# fullflex-1.net
KiCad netlist of a schematic drawn in Altium Designer
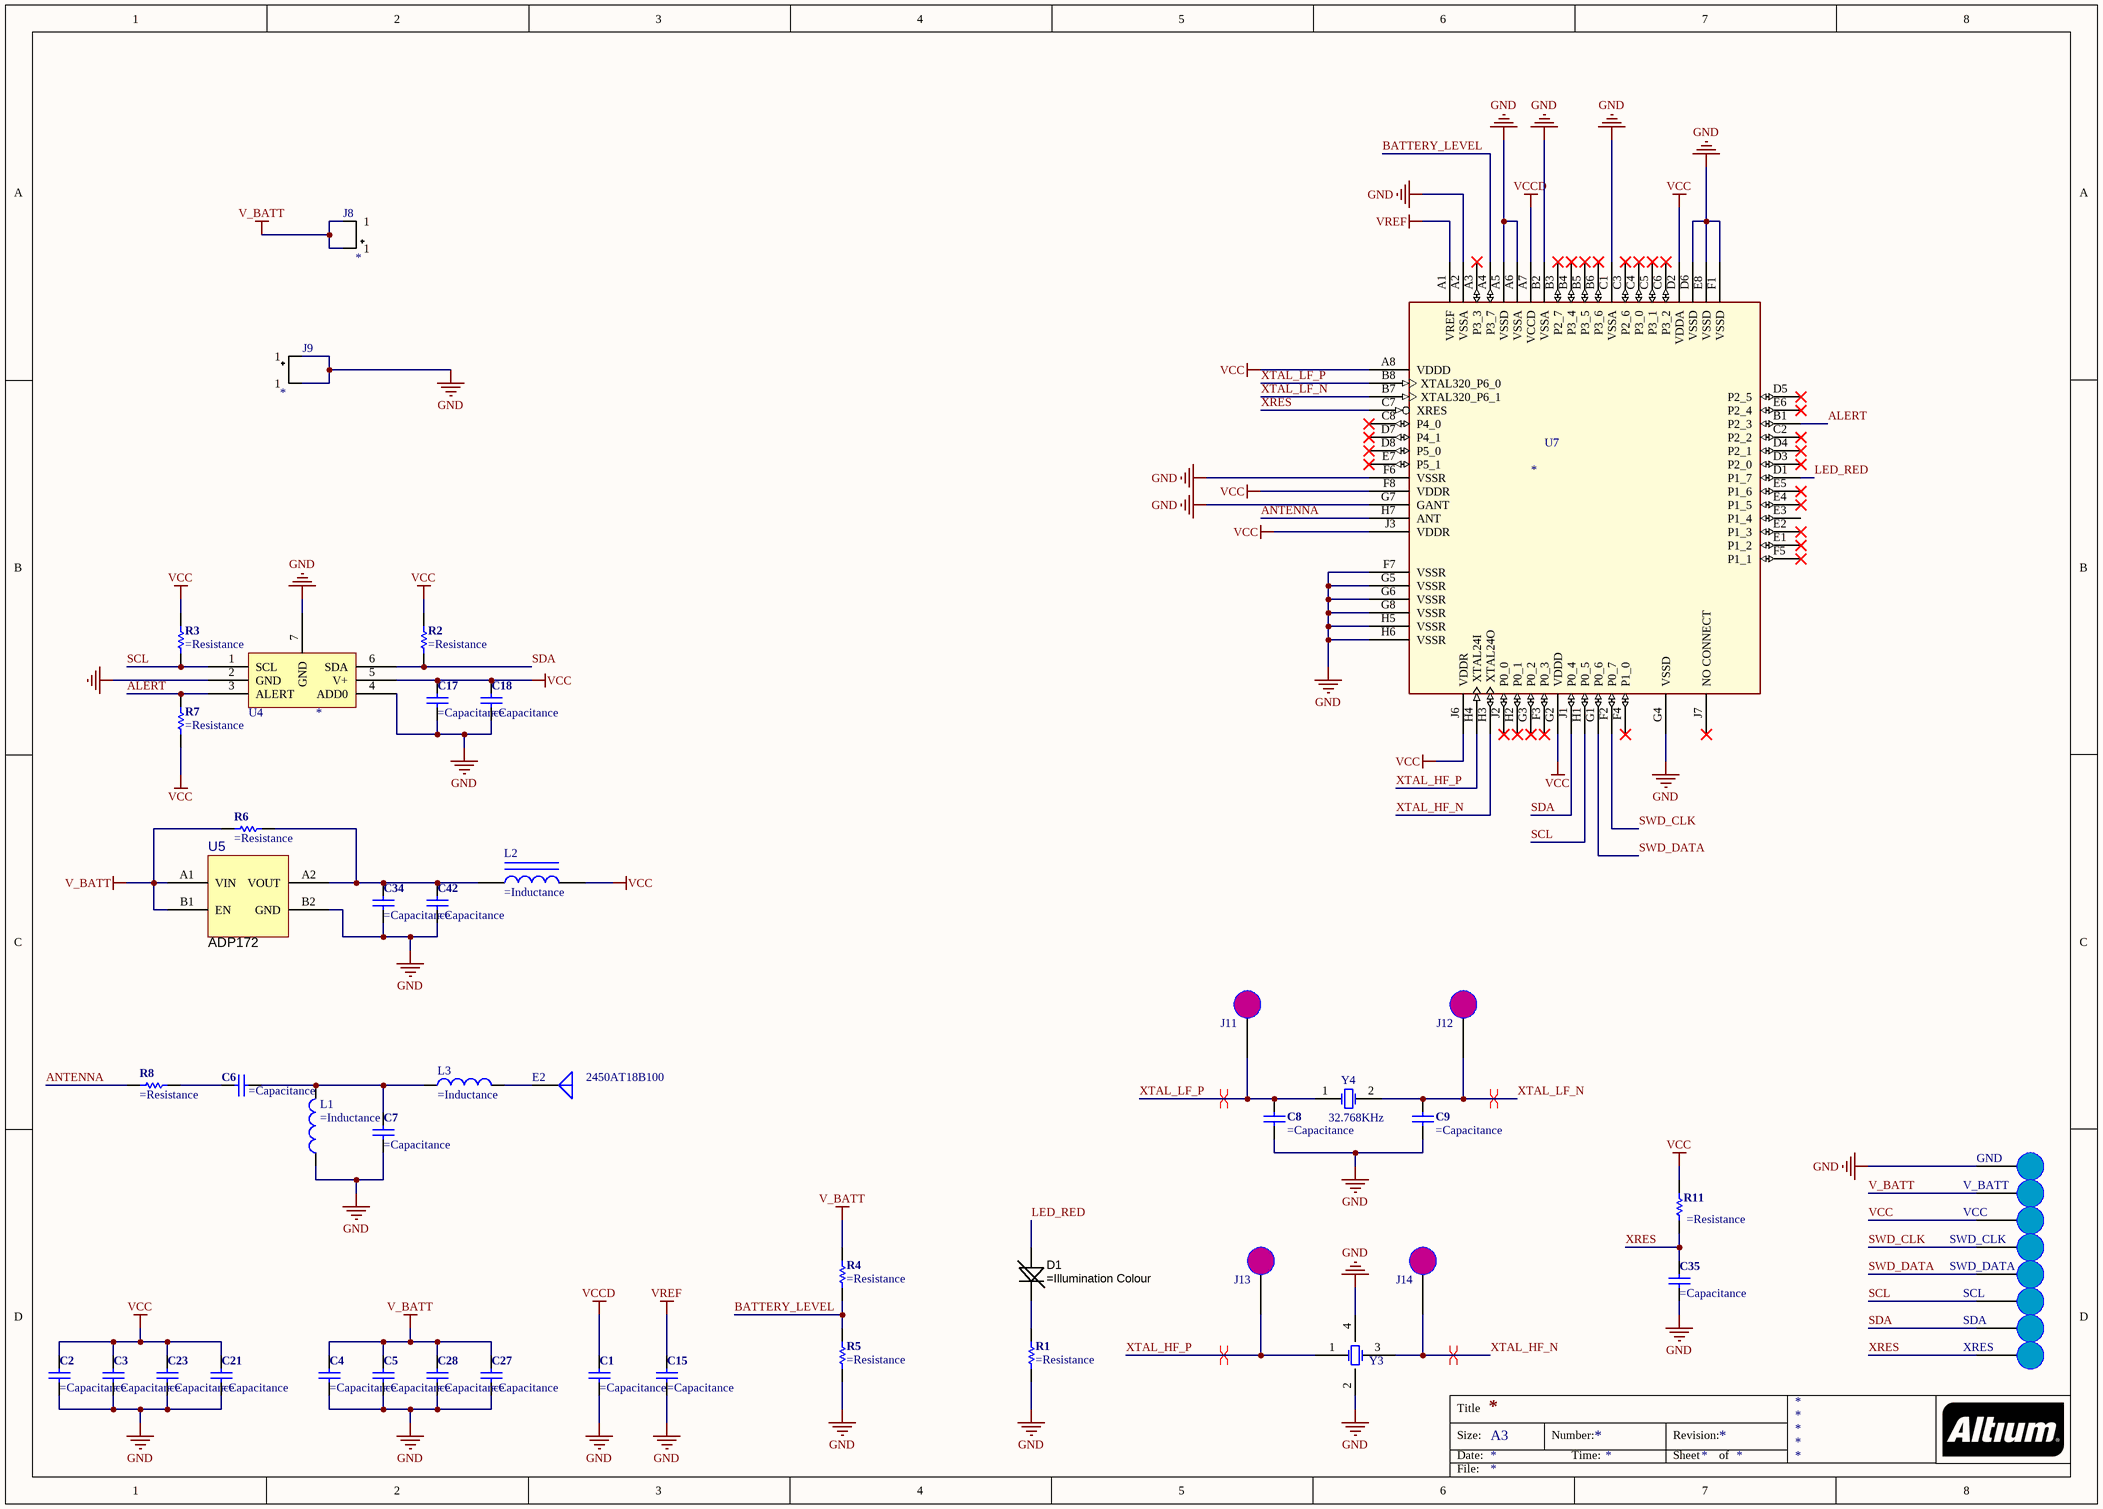
[diagram p0: fullflex-1.SchDoc]

(export (version "E")
  (design (tool "Eeschema 10.0.6"))
  (components
    (comp (ref "C1")
      (value "~")
      (footprint "CAP_0201(0603)_M")
      (description "___ OHM ___ mW 0201(0603) SMD")
      (libsource (lib "tempsensor") (part "C-0201(0603)"))
    )
    (comp (ref "C2")
      (value "~")
      (footprint "CAP_0402(1005)_M")
      (description "___ OHM ___ mW 0402(1005) SMD")
      (libsource (lib "tempsensor") (part "C-0402(1005)"))
    )
    (comp (ref "C3")
      (value "~")
      (footprint "CAP_0402(1005)_M")
      (description "___ OHM ___ mW 0402(1005) SMD")
      (libsource (lib "tempsensor") (part "C-0402(1005)"))
    )
    (comp (ref "C4")
      (value "~")
      (footprint "CAP_0402(1005)_M")
      (description "___ OHM ___ mW 0402(1005) SMD")
      (libsource (lib "tempsensor") (part "C-0402(1005)"))
    )
    (comp (ref "C5")
      (value "~")
      (footprint "CAP_0402(1005)_M")
      (description "___ OHM ___ mW 0402(1005) SMD")
      (libsource (lib "tempsensor") (part "C-0402(1005)"))
    )
    (comp (ref "C6")
      (value "~")
      (footprint "CAP_0402(1005)_M")
      (description "___ OHM ___ mW 0402(1005) SMD")
      (libsource (lib "tempsensor") (part "C-0402(1005)"))
    )
    (comp (ref "C7")
      (value "~")
      (footprint "CAP_0402(1005)_M")
      (description "___ OHM ___ mW 0402(1005) SMD")
      (libsource (lib "tempsensor") (part "C-0402(1005)"))
    )
    (comp (ref "C8")
      (value "~")
      (footprint "CAP_0402(1005)_M")
      (description "___ OHM ___ mW 0402(1005) SMD")
      (libsource (lib "tempsensor") (part "C-0402(1005)"))
    )
    (comp (ref "C9")
      (value "~")
      (footprint "CAP_0402(1005)_M")
      (description "___ OHM ___ mW 0402(1005) SMD")
      (libsource (lib "tempsensor") (part "C-0402(1005)"))
    )
    (comp (ref "C15")
      (value "~")
      (footprint "CAP_0201(0603)_M")
      (description "___ OHM ___ mW 0201(0603) SMD")
      (libsource (lib "tempsensor") (part "C-0201(0603)"))
    )
    (comp (ref "C17")
      (value "~")
      (footprint "CAP_0201(0603)_M")
      (description "___ OHM ___ mW 0201(0603) SMD")
      (libsource (lib "tempsensor") (part "C-0201(0603)"))
    )
    (comp (ref "C18")
      (value "~")
      (footprint "CAP_0201(0603)_M")
      (description "___ OHM ___ mW 0201(0603) SMD")
      (libsource (lib "tempsensor") (part "C-0201(0603)"))
    )
    (comp (ref "C21")
      (value "~")
      (footprint "CAP_0201(0603)_M")
      (description "___ OHM ___ mW 0201(0603) SMD")
      (libsource (lib "tempsensor") (part "C-0201(0603)"))
    )
    (comp (ref "C23")
      (value "~")
      (footprint "CAP_0201(0603)_M")
      (description "___ OHM ___ mW 0201(0603) SMD")
      (libsource (lib "tempsensor") (part "C-0201(0603)"))
    )
    (comp (ref "C27")
      (value "~")
      (footprint "CAP_0201(0603)_M")
      (description "___ OHM ___ mW 0201(0603) SMD")
      (libsource (lib "tempsensor") (part "C-0201(0603)"))
    )
    (comp (ref "C28")
      (value "~")
      (footprint "CAP_0201(0603)_M")
      (description "___ OHM ___ mW 0201(0603) SMD")
      (libsource (lib "tempsensor") (part "C-0201(0603)"))
    )
    (comp (ref "C34")
      (value "~")
      (footprint "CAP_0201(0603)_M")
      (description "___ OHM ___ mW 0201(0603) SMD")
      (libsource (lib "tempsensor") (part "C-0201(0603)"))
    )
    (comp (ref "C35")
      (value "~")
      (footprint "CAP_0201(0603)_M")
      (description "___ OHM ___ mW 0201(0603) SMD")
      (libsource (lib "tempsensor") (part "C-0201(0603)"))
    )
    (comp (ref "C42")
      (value "~")
      (footprint "CAP_0201(0603)_M")
      (description "___ OHM ___ mW 0201(0603) SMD")
      (libsource (lib "tempsensor") (part "C-0201(0603)"))
    )
    (comp (ref "D1")
      (value "~")
      (footprint "LED_0402(1005)")
      (description "LED, 0402(1005) SMD")
      (libsource (lib "tempsensor") (part "LED_0402(1005)"))
    )
    (comp (ref "E2")
      (value "2450AT18B100")
      (footprint "2450AT18B100")
      (description "2.4 GHz BLE Antenna")
      (fields
        (field (name "MANUFACTURER") "Johanson")
        (field (name "MANUFACTURER PART NUMBER") "2450AT18B100E")
      )
      (libsource (lib "tempsensor") (part "2450AT18B100"))
    )
    (comp (ref "GND")
      (value "*")
      (footprint "Pogo-Pin-Pad")
      (libsource (lib "tempsensor") (part "Probe-Pin Pad"))
    )
    (comp (ref "J8")
      (value "*")
      (footprint "Battery_PAD")
      (libsource (lib "tempsensor") (part "Battery_Connector"))
    )
    (comp (ref "J9")
      (value "*")
      (footprint "Battery_PAD")
      (libsource (lib "tempsensor") (part "Battery_Connector"))
    )
    (comp (ref "J11")
      (value "*")
      (footprint "Pogo-CLOCK-PAD")
      (libsource (lib "tempsensor") (part "Probe-CLOCK"))
    )
    (comp (ref "J12")
      (value "*")
      (footprint "Pogo-CLOCK-PAD")
      (libsource (lib "tempsensor") (part "Probe-CLOCK"))
    )
    (comp (ref "J13")
      (value "*")
      (footprint "Pogo-CLOCK-PAD")
      (libsource (lib "tempsensor") (part "Probe-CLOCK"))
    )
    (comp (ref "J14")
      (value "*")
      (footprint "Pogo-CLOCK-PAD")
      (libsource (lib "tempsensor") (part "Probe-CLOCK"))
    )
    (comp (ref "L1")
      (value "~")
      (footprint "IND_0402(1005)_M")
      (libsource (lib "tempsensor") (part "I-0402(1005)"))
    )
    (comp (ref "L2")
      (value "~")
      (footprint "IND_0402(1005)_M")
      (description "Magnetic-Core Inductor")
      (libsource (lib "tempsensor") (part "Inductor Iron"))
    )
    (comp (ref "L3")
      (value "~")
      (footprint "IND_0402(1005)_M")
      (libsource (lib "tempsensor") (part "I-0402(1005)"))
    )
    (comp (ref "R1")
      (value "~")
      (footprint "RES_0201(0603)_M")
      (description "___ OHM ___ mW 0201(0603) SMD")
      (libsource (lib "tempsensor") (part "R-0201(0603)"))
    )
    (comp (ref "R2")
      (value "~")
      (footprint "RES_0201(0603)_M")
      (description "___ OHM ___ mW 0201(0603) SMD")
      (libsource (lib "tempsensor") (part "R-0201(0603)"))
    )
    (comp (ref "R3")
      (value "~")
      (footprint "RES_0201(0603)_M")
      (description "___ OHM ___ mW 0201(0603) SMD")
      (libsource (lib "tempsensor") (part "R-0201(0603)"))
    )
    (comp (ref "R4")
      (value "~")
      (footprint "RES_0201(0603)_M")
      (description "___ OHM ___ mW 0201(0603) SMD")
      (libsource (lib "tempsensor") (part "R-0201(0603)"))
    )
    (comp (ref "R5")
      (value "~")
      (footprint "RES_0201(0603)_M")
      (description "___ OHM ___ mW 0201(0603) SMD")
      (libsource (lib "tempsensor") (part "R-0201(0603)"))
    )
    (comp (ref "R6")
      (value "~")
      (footprint "RES_0402(1005)_M")
      (description "___ OHM ___ mW 0402(1005) SMD")
      (libsource (lib "tempsensor") (part "R-0402(1005)"))
    )
    (comp (ref "R7")
      (value "~")
      (footprint "RES_0201(0603)_M")
      (description "___ OHM ___ mW 0201(0603) SMD")
      (libsource (lib "tempsensor") (part "R-0201(0603)"))
    )
    (comp (ref "R8")
      (value "~")
      (footprint "RES_0402(1005)_M")
      (description "___ OHM ___ mW 0402(1005) SMD")
      (libsource (lib "tempsensor") (part "R-0402(1005)"))
    )
    (comp (ref "R11")
      (value "~")
      (footprint "RES_0201(0603)_M")
      (description "___ OHM ___ mW 0201(0603) SMD")
      (libsource (lib "tempsensor") (part "R-0201(0603)"))
    )
    (comp (ref "SCL")
      (value "*")
      (footprint "Pogo-Pin-Pad")
      (libsource (lib "tempsensor") (part "Probe-Pin Pad"))
    )
    (comp (ref "SDA")
      (value "*")
      (footprint "Pogo-Pin-Pad")
      (libsource (lib "tempsensor") (part "Probe-Pin Pad"))
    )
    (comp (ref "SWD_CLK")
      (value "*")
      (footprint "Pogo-Pin-Pad")
      (libsource (lib "tempsensor") (part "Probe-Pin Pad"))
    )
    (comp (ref "SWD_DATA")
      (value "*")
      (footprint "Pogo-Pin-Pad")
      (libsource (lib "tempsensor") (part "Probe-Pin Pad"))
    )
    (comp (ref "U4")
      (value "*")
      (footprint "WSON-6")
      (description "TI Digital I2C Temperature Sensor")
      (fields
        (field (name "MANUFACTURER") "Texas Instruments")
        (field (name "MANUFACTURER PART NUMBER") "TMP116AIDRVT")
      )
      (libsource (lib "tempsensor") (part "TMP116"))
    )
    (comp (ref "U5")
      (value "ADP172")
      (footprint "ADP172")
      (description "3V LDO")
      (fields
        (field (name "MANUFACTURER") "Analog Devices")
        (field (name "MANUFACTURER PART NUMBER") "ADP172ACBZ-3.0-R7")
      )
      (libsource (lib "tempsensor") (part "ADP172"))
    )
    (comp (ref "U7")
      (value "*")
      (footprint "WLCSP-68")
      (description "PSOC 4 CYBLE")
      (fields
        (field (name "MANUFACTURER") "Cypress")
        (field (name "MANUFACTURER PART NUMBER") "CY8C4247FNI-BL483T")
      )
      (libsource (lib "tempsensor") (part "CY8C4127FNI-BL483"))
    )
    (comp (ref "VCC")
      (value "*")
      (footprint "Pogo-Pin-Pad")
      (libsource (lib "tempsensor") (part "Probe-Pin Pad"))
    )
    (comp (ref "V_BATT")
      (value "*")
      (footprint "Pogo-Pin-Pad")
      (libsource (lib "tempsensor") (part "Probe-Pin Pad"))
    )
    (comp (ref "XRES")
      (value "*")
      (footprint "Pogo-Pin-Pad")
      (libsource (lib "tempsensor") (part "Probe-Pin Pad"))
    )
    (comp (ref "Y3")
      (value "ECX-2236")
      (footprint "ECX-2236")
      (description "24 MHz Crystal")
      (fields
        (field (name "MANUFACTURER") "ECS International")
        (field (name "MANUFACTURER PART NUMBER") "ECS-240-8-36CKM-TR")
      )
      (libsource (lib "tempsensor") (part "ECX-2236"))
    )
    (comp (ref "Y4")
      (value "32.768KHz")
      (footprint "ABS05")
      (description "Crystal Oscillator")
      (fields
        (field (name "MANUFACTURER") "Abracon")
        (field (name "MANUFACTURER PART NUMBER") "ABS05-32.768KHZ-T")
      )
      (libsource (lib "tempsensor") (part "ABS05"))
    )
  )
  (nets
    (net (code "1") (name "/ALERT") (class "Default")
      (node (ref "R7") (pin "1") (pinfunction "1_1") (pintype "passive"))
      (node (ref "U4") (pin "3") (pinfunction "ALERT_3") (pintype "passive"))
      (node (ref "U7") (pin "B1") (pinfunction "P2_3_B1") (pintype "bidirectional"))
    )
    (net (code "2") (name "/ANTENNA") (class "Default")
      (node (ref "R8") (pin "1") (pinfunction "1_1") (pintype "passive"))
      (node (ref "U7") (pin "H7") (pinfunction "ANT_H7") (pintype "passive"))
    )
    (net (code "3") (name "/BATTERY_LEVEL") (class "Default")
      (node (ref "R4") (pin "2") (pinfunction "2_2") (pintype "passive"))
      (node (ref "R5") (pin "1") (pinfunction "1_1") (pintype "passive"))
      (node (ref "U7") (pin "A4") (pinfunction "P3_7_A4") (pintype "bidirectional"))
    )
    (net (code "4") (name "/LED_RED") (class "Default")
      (node (ref "D1") (pin "A") (pinfunction "A_A") (pintype "passive"))
      (node (ref "U7") (pin "D1") (pinfunction "P1_7_D1") (pintype "bidirectional"))
    )
    (net (code "5") (name "/SCL") (class "Default")
      (node (ref "R3") (pin "2") (pinfunction "2_2") (pintype "passive"))
      (node (ref "SCL") (pin "1") (pinfunction "1_1") (pintype "passive"))
      (node (ref "U4") (pin "1") (pinfunction "SCL_1") (pintype "passive"))
      (node (ref "U7") (pin "H1") (pinfunction "P0_5_H1") (pintype "bidirectional"))
    )
    (net (code "6") (name "/SDA") (class "Default")
      (node (ref "R2") (pin "2") (pinfunction "2_2") (pintype "passive"))
      (node (ref "SDA") (pin "1") (pinfunction "1_1") (pintype "passive"))
      (node (ref "U4") (pin "6") (pinfunction "SDA_6") (pintype "passive"))
      (node (ref "U7") (pin "J1") (pinfunction "P0_4_J1") (pintype "bidirectional"))
    )
    (net (code "7") (name "/SWD_CLK") (class "Default")
      (node (ref "SWD_CLK") (pin "1") (pinfunction "1_1") (pintype "passive"))
      (node (ref "U7") (pin "F2") (pinfunction "P0_7_F2") (pintype "bidirectional"))
    )
    (net (code "8") (name "/SWD_DATA") (class "Default")
      (node (ref "SWD_DATA") (pin "1") (pinfunction "1_1") (pintype "passive"))
      (node (ref "U7") (pin "G1") (pinfunction "P0_6_G1") (pintype "bidirectional"))
    )
    (net (code "9") (name "/XRES") (class "Default")
      (node (ref "C35") (pin "1") (pinfunction "1_1") (pintype "passive"))
      (node (ref "R11") (pin "2") (pinfunction "2_2") (pintype "passive"))
      (node (ref "U7") (pin "C7") (pinfunction "XRES_C7") (pintype "input"))
      (node (ref "XRES") (pin "1") (pinfunction "1_1") (pintype "passive"))
    )
    (net (code "10") (name "/XTAL_HF_N") (class "Default")
      (node (ref "J14") (pin "1") (pinfunction "1_1") (pintype "passive"))
      (node (ref "U7") (pin "H3") (pinfunction "XTAL24O_H3") (pintype "bidirectional"))
      (node (ref "Y3") (pin "3") (pinfunction "OSC2_3") (pintype "passive"))
    )
    (net (code "11") (name "/XTAL_HF_P") (class "Default")
      (node (ref "J13") (pin "1") (pinfunction "1_1") (pintype "passive"))
      (node (ref "U7") (pin "H4") (pinfunction "XTAL24I_H4") (pintype "input"))
      (node (ref "Y3") (pin "1") (pinfunction "OSC1_1") (pintype "passive"))
    )
    (net (code "12") (name "/XTAL_LF_N") (class "Default")
      (node (ref "C9") (pin "1") (pinfunction "1_1") (pintype "passive"))
      (node (ref "J12") (pin "1") (pinfunction "1_1") (pintype "passive"))
      (node (ref "U7") (pin "B7") (pinfunction "XTAL320_P6_1_B7") (pintype "input"))
      (node (ref "Y4") (pin "2") (pinfunction "OSC2_2") (pintype "passive"))
    )
    (net (code "13") (name "/XTAL_LF_P") (class "Default")
      (node (ref "C8") (pin "1") (pinfunction "1_1") (pintype "passive"))
      (node (ref "J11") (pin "1") (pinfunction "1_1") (pintype "passive"))
      (node (ref "U7") (pin "B8") (pinfunction "XTAL320_P6_0_B8") (pintype "input"))
      (node (ref "Y4") (pin "1") (pinfunction "OSC1_1") (pintype "passive"))
    )
    (net (code "14") (name "GND") (class "Default")
      (node (ref "C1") (pin "2") (pinfunction "2_2") (pintype "passive"))
      (node (ref "C15") (pin "2") (pinfunction "2_2") (pintype "passive"))
      (node (ref "C17") (pin "2") (pinfunction "2_2") (pintype "passive"))
      (node (ref "C18") (pin "2") (pinfunction "2_2") (pintype "passive"))
      (node (ref "C2") (pin "2") (pinfunction "2_2") (pintype "passive"))
      (node (ref "C21") (pin "2") (pinfunction "2_2") (pintype "passive"))
      (node (ref "C23") (pin "2") (pinfunction "2_2") (pintype "passive"))
      (node (ref "C27") (pin "2") (pinfunction "2_2") (pintype "passive"))
      (node (ref "C28") (pin "2") (pinfunction "2_2") (pintype "passive"))
      (node (ref "C3") (pin "2") (pinfunction "2_2") (pintype "passive"))
      (node (ref "C34") (pin "2") (pinfunction "2_2") (pintype "passive"))
      (node (ref "C35") (pin "2") (pinfunction "2_2") (pintype "passive"))
      (node (ref "C4") (pin "2") (pinfunction "2_2") (pintype "passive"))
      (node (ref "C42") (pin "2") (pinfunction "2_2") (pintype "passive"))
      (node (ref "C5") (pin "2") (pinfunction "2_2") (pintype "passive"))
      (node (ref "C7") (pin "2") (pinfunction "2_2") (pintype "passive"))
      (node (ref "C8") (pin "2") (pinfunction "2_2") (pintype "passive"))
      (node (ref "C9") (pin "2") (pinfunction "2_2") (pintype "passive"))
      (node (ref "GND") (pin "1") (pinfunction "1_1") (pintype "passive"))
      (node (ref "J9") (pin "1") (pinfunction "1_1") (pintype "passive"))
      (node (ref "L1") (pin "1") (pinfunction "1_1") (pintype "passive"))
      (node (ref "R1") (pin "2") (pinfunction "2_2") (pintype "passive"))
      (node (ref "R5") (pin "2") (pinfunction "2_2") (pintype "passive"))
      (node (ref "U4") (pin "2") (pinfunction "GND_2") (pintype "passive"))
      (node (ref "U4") (pin "4") (pinfunction "ADD0_4") (pintype "passive"))
      (node (ref "U4") (pin "7") (pinfunction "GND_7") (pintype "passive"))
      (node (ref "U5") (pin "B2") (pinfunction "GND_B2") (pintype "passive"))
      (node (ref "U7") (pin "A2") (pinfunction "VSSA_A2") (pintype "power_in"))
      (node (ref "U7") (pin "A5") (pinfunction "VSSD_A5") (pintype "power_in"))
      (node (ref "U7") (pin "A6") (pinfunction "VSSA_A6") (pintype "power_in"))
      (node (ref "U7") (pin "B2") (pinfunction "VSSA_B2") (pintype "power_in"))
      (node (ref "U7") (pin "C1") (pinfunction "VSSA_C1") (pintype "power_in"))
      (node (ref "U7") (pin "D6") (pinfunction "VSSD_D6") (pintype "power_in"))
      (node (ref "U7") (pin "E8") (pinfunction "VSSD_E8") (pintype "power_in"))
      (node (ref "U7") (pin "F1") (pinfunction "VSSD_F1") (pintype "power_in"))
      (node (ref "U7") (pin "F6") (pinfunction "VSSR_F6") (pintype "power_in"))
      (node (ref "U7") (pin "F7") (pinfunction "VSSR_F7") (pintype "power_in"))
      (node (ref "U7") (pin "G4") (pinfunction "VSSD_G4") (pintype "power_in"))
      (node (ref "U7") (pin "G5") (pinfunction "VSSR_G5") (pintype "power_in"))
      (node (ref "U7") (pin "G6") (pinfunction "VSSR_G6") (pintype "power_in"))
      (node (ref "U7") (pin "G7") (pinfunction "GANT_G7") (pintype "power_in"))
      (node (ref "U7") (pin "G8") (pinfunction "VSSR_G8") (pintype "power_in"))
      (node (ref "U7") (pin "H5") (pinfunction "VSSR_H5") (pintype "power_in"))
      (node (ref "U7") (pin "H6") (pinfunction "VSSR_H6") (pintype "power_in"))
      (node (ref "Y3") (pin "2") (pinfunction "GND_2") (pintype "passive"))
      (node (ref "Y3") (pin "4") (pinfunction "GND_4") (pintype "passive"))
    )
    (net (code "15") (name "Net-(C6-Pad1)") (class "Default")
      (node (ref "C6") (pin "1") (pinfunction "1_1") (pintype "passive"))
      (node (ref "R8") (pin "2") (pinfunction "2_2") (pintype "passive"))
    )
    (net (code "16") (name "Net-(C6-Pad2)") (class "Default")
      (node (ref "C6") (pin "2") (pinfunction "2_2") (pintype "passive"))
      (node (ref "C7") (pin "1") (pinfunction "1_1") (pintype "passive"))
      (node (ref "L1") (pin "2") (pinfunction "2_2") (pintype "passive"))
      (node (ref "L3") (pin "1") (pinfunction "1_1") (pintype "passive"))
    )
    (net (code "17") (name "Net-(D1-PadK)") (class "Default")
      (node (ref "D1") (pin "K") (pinfunction "K_K") (pintype "passive"))
      (node (ref "R1") (pin "1") (pinfunction "1_1") (pintype "passive"))
    )
    (net (code "18") (name "Net-(E2-A)") (class "Default")
      (node (ref "E2") (pin "1") (pinfunction "A_1") (pintype "passive"))
      (node (ref "L3") (pin "2") (pinfunction "2_2") (pintype "passive"))
    )
    (net (code "19") (name "Net-(U5-VOUT)") (class "Default")
      (node (ref "C34") (pin "1") (pinfunction "1_1") (pintype "passive"))
      (node (ref "C42") (pin "1") (pinfunction "1_1") (pintype "passive"))
      (node (ref "L2") (pin "1") (pinfunction "1_1") (pintype "passive"))
      (node (ref "R6") (pin "2") (pinfunction "2_2") (pintype "passive"))
      (node (ref "U5") (pin "A2") (pinfunction "VOUT_A2") (pintype "passive"))
    )
    (net (code "20") (name "VCC") (class "Default")
      (node (ref "C17") (pin "1") (pinfunction "1_1") (pintype "passive"))
      (node (ref "C18") (pin "1") (pinfunction "1_1") (pintype "passive"))
      (node (ref "C2") (pin "1") (pinfunction "1_1") (pintype "passive"))
      (node (ref "C21") (pin "1") (pinfunction "1_1") (pintype "passive"))
      (node (ref "C23") (pin "1") (pinfunction "1_1") (pintype "passive"))
      (node (ref "C3") (pin "1") (pinfunction "1_1") (pintype "passive"))
      (node (ref "L2") (pin "2") (pinfunction "2_2") (pintype "passive"))
      (node (ref "R11") (pin "1") (pinfunction "1_1") (pintype "passive"))
      (node (ref "R2") (pin "1") (pinfunction "1_1") (pintype "passive"))
      (node (ref "R3") (pin "1") (pinfunction "1_1") (pintype "passive"))
      (node (ref "R7") (pin "2") (pinfunction "2_2") (pintype "passive"))
      (node (ref "U4") (pin "5") (pinfunction "V+_5") (pintype "passive"))
      (node (ref "U7") (pin "A8") (pinfunction "VDDD_A8") (pintype "power_in"))
      (node (ref "U7") (pin "D2") (pinfunction "VDDA_D2") (pintype "power_in"))
      (node (ref "U7") (pin "F8") (pinfunction "VDDR_F8") (pintype "power_in"))
      (node (ref "U7") (pin "G2") (pinfunction "VDDD_G2") (pintype "power_in"))
      (node (ref "U7") (pin "J3") (pinfunction "VDDR_J3") (pintype "power_in"))
      (node (ref "U7") (pin "J6") (pinfunction "VDDR_J6") (pintype "power_in"))
      (node (ref "VCC") (pin "1") (pinfunction "1_1") (pintype "passive"))
    )
    (net (code "21") (name "VCCD") (class "Default")
      (node (ref "C1") (pin "1") (pinfunction "1_1") (pintype "passive"))
      (node (ref "U7") (pin "A7") (pinfunction "VCCD_A7") (pintype "power_in"))
    )
    (net (code "22") (name "VREF") (class "Default")
      (node (ref "C15") (pin "1") (pinfunction "1_1") (pintype "passive"))
      (node (ref "U7") (pin "A1") (pinfunction "VREF_A1") (pintype "power_in"))
    )
    (net (code "23") (name "V_BATT") (class "Default")
      (node (ref "C27") (pin "1") (pinfunction "1_1") (pintype "passive"))
      (node (ref "C28") (pin "1") (pinfunction "1_1") (pintype "passive"))
      (node (ref "C4") (pin "1") (pinfunction "1_1") (pintype "passive"))
      (node (ref "C5") (pin "1") (pinfunction "1_1") (pintype "passive"))
      (node (ref "J8") (pin "1") (pinfunction "1_1") (pintype "passive"))
      (node (ref "R4") (pin "1") (pinfunction "1_1") (pintype "passive"))
      (node (ref "R6") (pin "1") (pinfunction "1_1") (pintype "passive"))
      (node (ref "U5") (pin "A1") (pinfunction "VIN_A1") (pintype "passive"))
      (node (ref "U5") (pin "B1") (pinfunction "EN_B1") (pintype "passive"))
      (node (ref "V_BATT") (pin "1") (pinfunction "1_1") (pintype "passive"))
    )
    (net (code "24") (name "unconnected-(U7-NO_CONNECT-PadJ7)") (class "Default")
      (node (ref "U7") (pin "J7") (pinfunction "NO_CONNECT_J7") (pintype "passive+no_connect"))
    )
    (net (code "25") (name "unconnected-(U7-P0_0-PadJ2)") (class "Default")
      (node (ref "U7") (pin "J2") (pinfunction "P0_0_J2") (pintype "bidirectional+no_connect"))
    )
    (net (code "26") (name "unconnected-(U7-P0_1-PadH2)") (class "Default")
      (node (ref "U7") (pin "H2") (pinfunction "P0_1_H2") (pintype "bidirectional+no_connect"))
    )
    (net (code "27") (name "unconnected-(U7-P0_2-PadG3)") (class "Default")
      (node (ref "U7") (pin "G3") (pinfunction "P0_2_G3") (pintype "bidirectional+no_connect"))
    )
    (net (code "28") (name "unconnected-(U7-P0_3-PadF3)") (class "Default")
      (node (ref "U7") (pin "F3") (pinfunction "P0_3_F3") (pintype "bidirectional+no_connect"))
    )
    (net (code "29") (name "unconnected-(U7-P1_0-PadF4)") (class "Default")
      (node (ref "U7") (pin "F4") (pinfunction "P1_0_F4") (pintype "bidirectional+no_connect"))
    )
    (net (code "30") (name "unconnected-(U7-P1_1-PadF5)") (class "Default")
      (node (ref "U7") (pin "F5") (pinfunction "P1_1_F5") (pintype "bidirectional+no_connect"))
    )
    (net (code "31") (name "unconnected-(U7-P1_2-PadE1)") (class "Default")
      (node (ref "U7") (pin "E1") (pinfunction "P1_2_E1") (pintype "bidirectional+no_connect"))
    )
    (net (code "32") (name "unconnected-(U7-P1_3-PadE2)") (class "Default")
      (node (ref "U7") (pin "E2") (pinfunction "P1_3_E2") (pintype "bidirectional+no_connect"))
    )
    (net (code "33") (name "unconnected-(U7-P1_4-PadE3)") (class "Default")
      (node (ref "U7") (pin "E3") (pinfunction "P1_4_E3") (pintype "bidirectional"))
    )
    (net (code "34") (name "unconnected-(U7-P1_5-PadE4)") (class "Default")
      (node (ref "U7") (pin "E4") (pinfunction "P1_5_E4") (pintype "bidirectional+no_connect"))
    )
    (net (code "35") (name "unconnected-(U7-P1_6-PadE5)") (class "Default")
      (node (ref "U7") (pin "E5") (pinfunction "P1_6_E5") (pintype "bidirectional+no_connect"))
    )
    (net (code "36") (name "unconnected-(U7-P2_0-PadD3)") (class "Default")
      (node (ref "U7") (pin "D3") (pinfunction "P2_0_D3") (pintype "bidirectional+no_connect"))
    )
    (net (code "37") (name "unconnected-(U7-P2_1-PadD4)") (class "Default")
      (node (ref "U7") (pin "D4") (pinfunction "P2_1_D4") (pintype "bidirectional+no_connect"))
    )
    (net (code "38") (name "unconnected-(U7-P2_2-PadC2)") (class "Default")
      (node (ref "U7") (pin "C2") (pinfunction "P2_2_C2") (pintype "bidirectional+no_connect"))
    )
    (net (code "39") (name "unconnected-(U7-P2_4-PadE6)") (class "Default")
      (node (ref "U7") (pin "E6") (pinfunction "P2_4_E6") (pintype "bidirectional+no_connect"))
    )
    (net (code "40") (name "unconnected-(U7-P2_5-PadD5)") (class "Default")
      (node (ref "U7") (pin "D5") (pinfunction "P2_5_D5") (pintype "bidirectional+no_connect"))
    )
    (net (code "41") (name "unconnected-(U7-P2_6-PadC3)") (class "Default")
      (node (ref "U7") (pin "C3") (pinfunction "P2_6_C3") (pintype "bidirectional+no_connect"))
    )
    (net (code "42") (name "unconnected-(U7-P2_7-PadB3)") (class "Default")
      (node (ref "U7") (pin "B3") (pinfunction "P2_7_B3") (pintype "bidirectional+no_connect"))
    )
    (net (code "43") (name "unconnected-(U7-P3_0-PadC4)") (class "Default")
      (node (ref "U7") (pin "C4") (pinfunction "P3_0_C4") (pintype "bidirectional+no_connect"))
    )
    (net (code "44") (name "unconnected-(U7-P3_1-PadC5)") (class "Default")
      (node (ref "U7") (pin "C5") (pinfunction "P3_1_C5") (pintype "bidirectional+no_connect"))
    )
    (net (code "45") (name "unconnected-(U7-P3_2-PadC6)") (class "Default")
      (node (ref "U7") (pin "C6") (pinfunction "P3_2_C6") (pintype "bidirectional+no_connect"))
    )
    (net (code "46") (name "unconnected-(U7-P3_3-PadA3)") (class "Default")
      (node (ref "U7") (pin "A3") (pinfunction "P3_3_A3") (pintype "bidirectional+no_connect"))
    )
    (net (code "47") (name "unconnected-(U7-P3_4-PadB4)") (class "Default")
      (node (ref "U7") (pin "B4") (pinfunction "P3_4_B4") (pintype "bidirectional+no_connect"))
    )
    (net (code "48") (name "unconnected-(U7-P3_5-PadB5)") (class "Default")
      (node (ref "U7") (pin "B5") (pinfunction "P3_5_B5") (pintype "bidirectional+no_connect"))
    )
    (net (code "49") (name "unconnected-(U7-P3_6-PadB6)") (class "Default")
      (node (ref "U7") (pin "B6") (pinfunction "P3_6_B6") (pintype "bidirectional+no_connect"))
    )
    (net (code "50") (name "unconnected-(U7-P4_0-PadC8)") (class "Default")
      (node (ref "U7") (pin "C8") (pinfunction "P4_0_C8") (pintype "bidirectional+no_connect"))
    )
    (net (code "51") (name "unconnected-(U7-P4_1-PadD7)") (class "Default")
      (node (ref "U7") (pin "D7") (pinfunction "P4_1_D7") (pintype "bidirectional+no_connect"))
    )
    (net (code "52") (name "unconnected-(U7-P5_0-PadD8)") (class "Default")
      (node (ref "U7") (pin "D8") (pinfunction "P5_0_D8") (pintype "bidirectional+no_connect"))
    )
    (net (code "53") (name "unconnected-(U7-P5_1-PadE7)") (class "Default")
      (node (ref "U7") (pin "E7") (pinfunction "P5_1_E7") (pintype "bidirectional+no_connect"))
    )
  )
)
